# ContactSensor.net
KiCad netlist of a schematic drawn in EAGLE
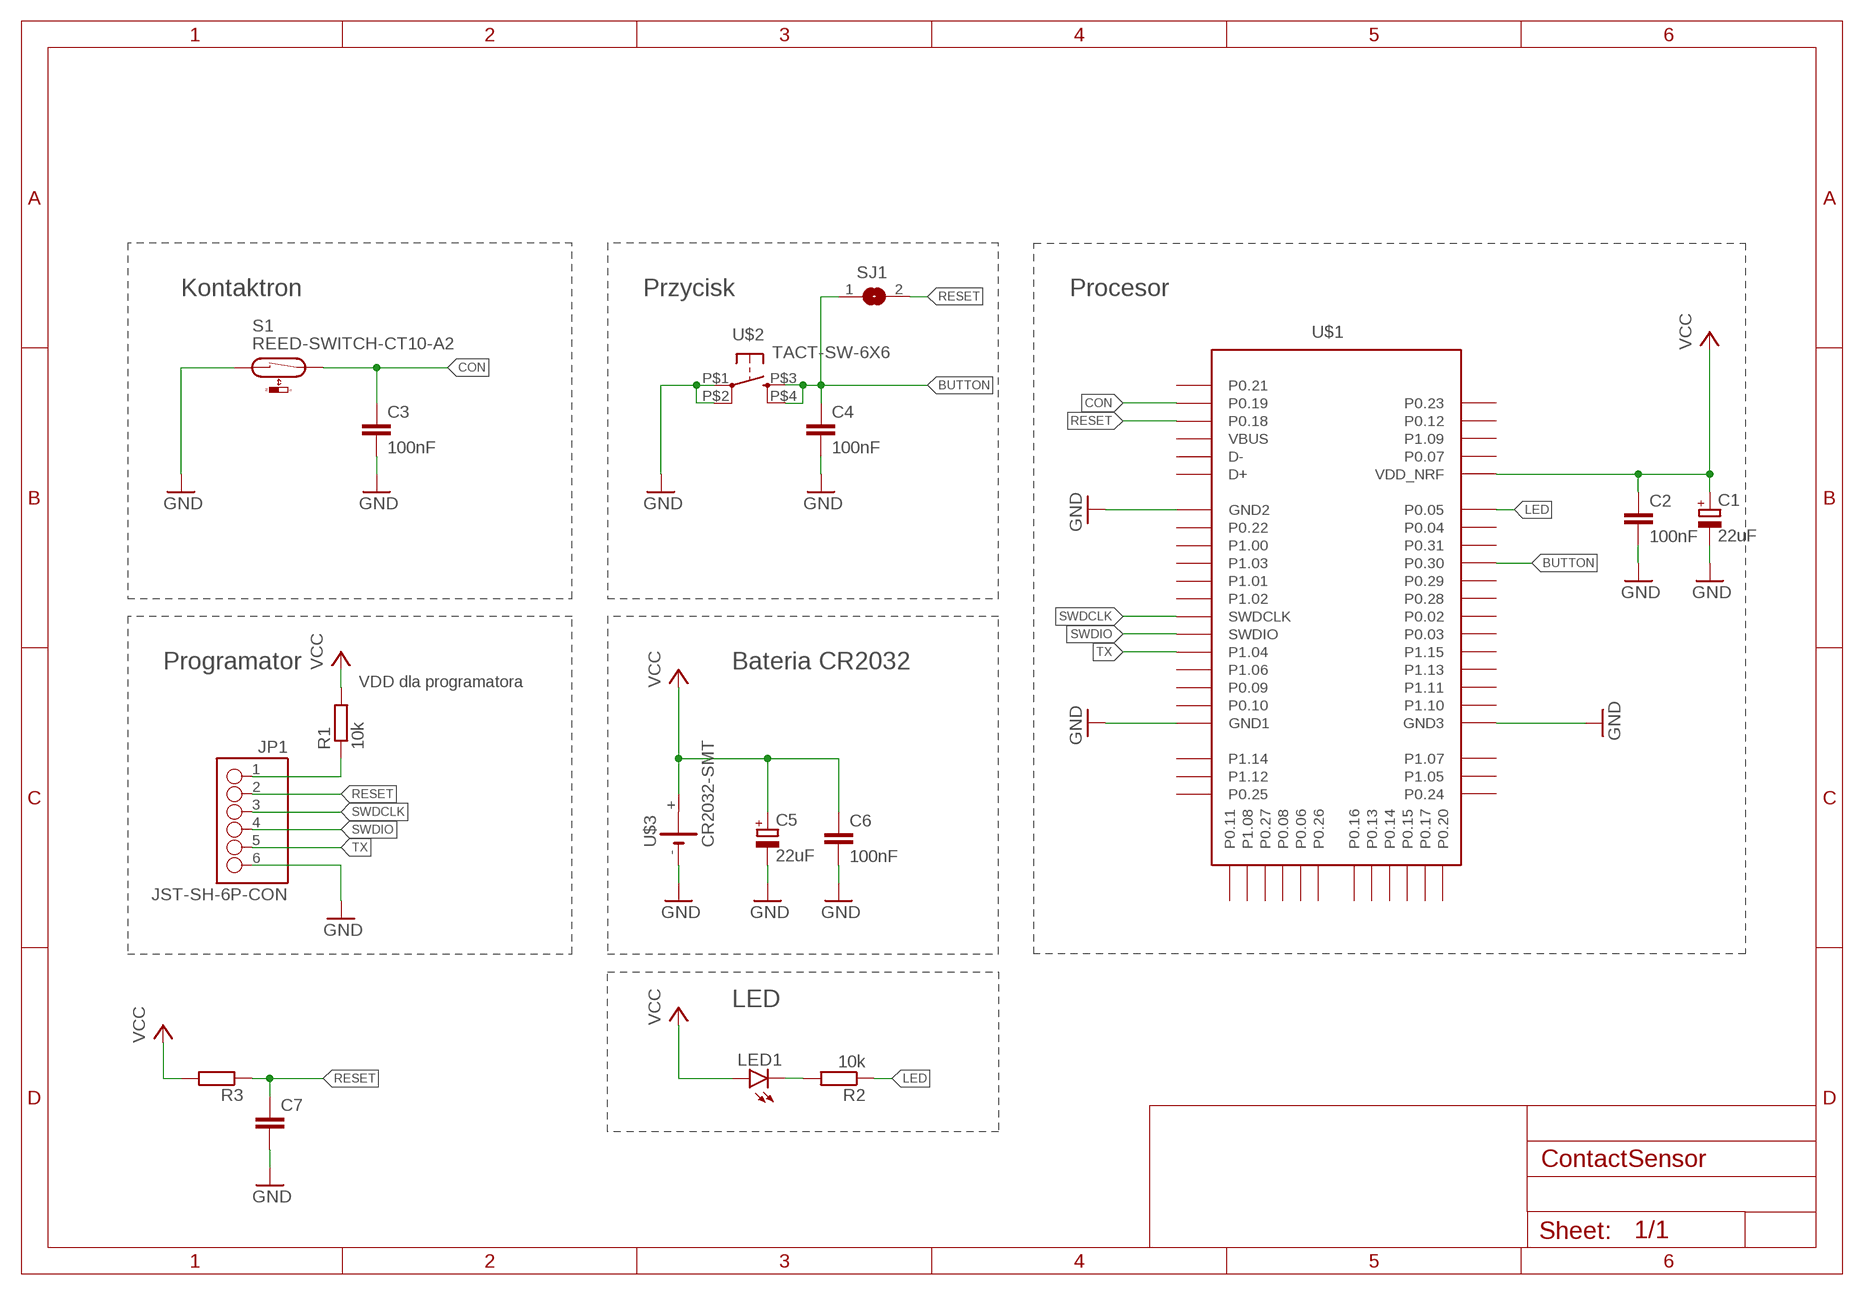
[diagram p0: schematic, sheet 1]

(export (version "E")
  (design (tool "Eeschema 10.0.6"))
  (components
    (comp (ref "C1")
      (value "22uF")
      (footprint "eagle-import:CT3528")
      (libsource (lib "eagle-import") (part "CPOL-EUCT3528"))
    )
    (comp (ref "C2")
      (value "100nF")
      (footprint "eagle-import:C0805K")
      (libsource (lib "eagle-import") (part "C-EUC0805K"))
    )
    (comp (ref "C3")
      (value "100nF")
      (footprint "eagle-import:C0805K")
      (libsource (lib "eagle-import") (part "C-EUC0805K"))
    )
    (comp (ref "C4")
      (value "100nF")
      (footprint "eagle-import:C0805K")
      (libsource (lib "eagle-import") (part "C-EUC0805K"))
    )
    (comp (ref "C5")
      (value "22uF")
      (footprint "eagle-import:CT3528")
      (libsource (lib "eagle-import") (part "CPOL-EUCT3528"))
    )
    (comp (ref "C6")
      (value "100nF")
      (footprint "eagle-import:C0805K")
      (libsource (lib "eagle-import") (part "C-EUC0805K"))
    )
    (comp (ref "C7")
      (value "C-EUC0603K")
      (footprint "eagle-import:C0603K")
      (libsource (lib "eagle-import") (part "C-EUC0603K"))
    )
    (comp (ref "JP1")
      (value "JST-SH-6P-CON")
      (footprint "eagle-import:JST-SH-6P-FOOT")
      (libsource (lib "eagle-import") (part "JST-SH-6P-CON"))
    )
    (comp (ref "LED1")
      (value "LEDCHIPLED_0603")
      (footprint "eagle-import:CHIPLED_0603")
      (libsource (lib "eagle-import") (part "LEDCHIPLED_0603"))
    )
    (comp (ref "R1")
      (value "10k")
      (footprint "eagle-import:R0603")
      (libsource (lib "eagle-import") (part "R-EU_R0603"))
    )
    (comp (ref "R2")
      (value "10k")
      (footprint "eagle-import:R0603")
      (libsource (lib "eagle-import") (part "R-EU_R0603"))
    )
    (comp (ref "R3")
      (value "R-EU_R0402")
      (footprint "eagle-import:R0402")
      (libsource (lib "eagle-import") (part "R-EU_R0402"))
    )
    (comp (ref "S1")
      (value "REED-SWITCH-CT10-A2")
      (footprint "eagle-import:CT10-A2")
      (libsource (lib "eagle-import") (part "REED-SWITCH-CT10-A2"))
    )
    (comp (ref "SJ1") (value "SJ") (footprint "eagle-import:SJ") (libsource (lib "eagle-import") (part "SJ")))
    (comp (ref "U$1")
      (value "HOLYIOT_18010")
      (footprint "eagle-import:PCBCOMPONENT_1")
      (libsource (lib "eagle-import") (part "HOLYIOT_18010"))
    )
    (comp (ref "U$2")
      (value "TACT-SW-6X6")
      (footprint "eagle-import:6X6-TACT-SWITCH-SMD")
      (libsource (lib "eagle-import") (part "TACT-SW-6X6"))
    )
    (comp (ref "U$3")
      (value "CR2032-SMT")
      (footprint "eagle-import:CR2032-SMT")
      (libsource (lib "eagle-import") (part "CR2032-SMT"))
    )
  )
  (nets
    (net (code "1") (name "BUTTON") (class "Default")
      (node (ref "C4") (pin "1") (pinfunction "1_1") (pintype "passive"))
      (node (ref "SJ1") (pin "1") (pinfunction "1_1") (pintype "passive"))
      (node (ref "U$1") (pin "P0.30") (pinfunction "P0.30_P0.30") (pintype "bidirectional"))
      (node (ref "U$2") (pin "P$3") (pinfunction "S_P$3") (pintype "passive"))
      (node (ref "U$2") (pin "P$4") (pinfunction "S1_P$4") (pintype "passive"))
    )
    (net (code "2") (name "CON") (class "Default")
      (node (ref "C3") (pin "1") (pinfunction "1_1") (pintype "passive"))
      (node (ref "S1") (pin "2") (pinfunction "2_2") (pintype "passive"))
      (node (ref "U$1") (pin "P0.19") (pinfunction "P0.19_P0.19") (pintype "bidirectional"))
    )
    (net (code "3") (name "GND") (class "Default")
      (node (ref "C1") (pin "-") (pinfunction "-_-") (pintype "passive"))
      (node (ref "C2") (pin "2") (pinfunction "2_2") (pintype "passive"))
      (node (ref "C3") (pin "2") (pinfunction "2_2") (pintype "passive"))
      (node (ref "C4") (pin "2") (pinfunction "2_2") (pintype "passive"))
      (node (ref "C5") (pin "-") (pinfunction "-_-") (pintype "passive"))
      (node (ref "C6") (pin "2") (pinfunction "2_2") (pintype "passive"))
      (node (ref "C7") (pin "2") (pinfunction "2_2") (pintype "passive"))
      (node (ref "JP1") (pin "6") (pinfunction "P$6_6") (pintype "bidirectional"))
      (node (ref "S1") (pin "1") (pinfunction "1_1") (pintype "passive"))
      (node (ref "U$1") (pin "GND") (pinfunction "GND1_GND") (pintype "bidirectional"))
      (node (ref "U$1") (pin "GND1") (pinfunction "GND2_GND1") (pintype "bidirectional"))
      (node (ref "U$1") (pin "GND2") (pinfunction "GND3_GND2") (pintype "bidirectional"))
      (node (ref "U$2") (pin "P$1") (pinfunction "P_P$1") (pintype "passive"))
      (node (ref "U$2") (pin "P$2") (pinfunction "P1_P$2") (pintype "passive"))
      (node (ref "U$3") (pin "-") (pinfunction "-_-") (pintype "passive"))
    )
    (net (code "4") (name "LED") (class "Default")
      (node (ref "R2") (pin "1") (pinfunction "1_1") (pintype "passive"))
      (node (ref "U$1") (pin "P0.05") (pinfunction "P0.05_P0.05") (pintype "bidirectional"))
    )
    (net (code "5") (name "Net-(JP1-P$1)") (class "Default")
      (node (ref "JP1") (pin "1") (pinfunction "P$1_1") (pintype "bidirectional"))
      (node (ref "R1") (pin "1") (pinfunction "1_1") (pintype "passive"))
    )
    (net (code "6") (name "Net-(LED1-PadC)") (class "Default")
      (node (ref "LED1") (pin "C") (pinfunction "C_C") (pintype "passive"))
      (node (ref "R2") (pin "2") (pinfunction "2_2") (pintype "passive"))
    )
    (net (code "7") (name "RESET") (class "Default")
      (node (ref "C7") (pin "1") (pinfunction "1_1") (pintype "passive"))
      (node (ref "JP1") (pin "2") (pinfunction "P$2_2") (pintype "bidirectional"))
      (node (ref "R3") (pin "1") (pinfunction "1_1") (pintype "passive"))
      (node (ref "SJ1") (pin "2") (pinfunction "2_2") (pintype "passive"))
      (node (ref "U$1") (pin "P0.18") (pinfunction "P0.18_P0.18") (pintype "bidirectional"))
    )
    (net (code "8") (name "SWDCLK") (class "Default")
      (node (ref "JP1") (pin "3") (pinfunction "P$3_3") (pintype "bidirectional"))
      (node (ref "U$1") (pin "SWDCLK") (pinfunction "SWDCLK_SWDCLK") (pintype "bidirectional"))
    )
    (net (code "9") (name "SWDIO") (class "Default")
      (node (ref "JP1") (pin "4") (pinfunction "P$4_4") (pintype "bidirectional"))
      (node (ref "U$1") (pin "SWDIO") (pinfunction "SWDIO_SWDIO") (pintype "bidirectional"))
    )
    (net (code "10") (name "TX") (class "Default")
      (node (ref "JP1") (pin "5") (pinfunction "P$5_5") (pintype "bidirectional"))
      (node (ref "U$1") (pin "P1.04") (pinfunction "P1.04_P1.04") (pintype "bidirectional"))
    )
    (net (code "11") (name "VCC") (class "Default")
      (node (ref "C1") (pin "+") (pinfunction "+_+") (pintype "passive"))
      (node (ref "C2") (pin "1") (pinfunction "1_1") (pintype "passive"))
      (node (ref "C5") (pin "+") (pinfunction "+_+") (pintype "passive"))
      (node (ref "C6") (pin "1") (pinfunction "1_1") (pintype "passive"))
      (node (ref "LED1") (pin "A") (pinfunction "A_A") (pintype "passive"))
      (node (ref "R1") (pin "2") (pinfunction "2_2") (pintype "passive"))
      (node (ref "R3") (pin "2") (pinfunction "2_2") (pintype "passive"))
      (node (ref "U$1") (pin "VDD_NRF") (pinfunction "VDD_NRF_VDD_NRF") (pintype "bidirectional"))
      (node (ref "U$3") (pin "+") (pinfunction "+_+") (pintype "passive"))
    )
    (net (code "12") (name "unconnected-(U$1-PadD+)") (class "Default")
      (node (ref "U$1") (pin "D+") (pinfunction "D+_D+") (pintype "bidirectional"))
    )
    (net (code "13") (name "unconnected-(U$1-PadD-)") (class "Default")
      (node (ref "U$1") (pin "D-") (pinfunction "D-_D-") (pintype "bidirectional"))
    )
    (net (code "14") (name "unconnected-(U$1-PadP0.02)") (class "Default")
      (node (ref "U$1") (pin "P0.02") (pinfunction "P0.02_P0.02") (pintype "bidirectional"))
    )
    (net (code "15") (name "unconnected-(U$1-PadP0.03)") (class "Default")
      (node (ref "U$1") (pin "P0.03") (pinfunction "P0.03_P0.03") (pintype "bidirectional"))
    )
    (net (code "16") (name "unconnected-(U$1-PadP0.04)") (class "Default")
      (node (ref "U$1") (pin "P0.04") (pinfunction "P0.04_P0.04") (pintype "bidirectional"))
    )
    (net (code "17") (name "unconnected-(U$1-PadP0.06)") (class "Default")
      (node (ref "U$1") (pin "P0.06") (pinfunction "P0.06_P0.06") (pintype "bidirectional"))
    )
    (net (code "18") (name "unconnected-(U$1-PadP0.07)") (class "Default")
      (node (ref "U$1") (pin "P0.07") (pinfunction "P0.07_P0.07") (pintype "bidirectional"))
    )
    (net (code "19") (name "unconnected-(U$1-PadP0.08)") (class "Default")
      (node (ref "U$1") (pin "P0.08") (pinfunction "P0.08_P0.08") (pintype "bidirectional"))
    )
    (net (code "20") (name "unconnected-(U$1-PadP0.09)") (class "Default")
      (node (ref "U$1") (pin "P0.09") (pinfunction "P0.09_P0.09") (pintype "bidirectional"))
    )
    (net (code "21") (name "unconnected-(U$1-PadP0.10)") (class "Default")
      (node (ref "U$1") (pin "P0.10") (pinfunction "P0.10_P0.10") (pintype "bidirectional"))
    )
    (net (code "22") (name "unconnected-(U$1-PadP0.11)") (class "Default")
      (node (ref "U$1") (pin "P0.11") (pinfunction "P0.11_P0.11") (pintype "bidirectional"))
    )
    (net (code "23") (name "unconnected-(U$1-PadP0.12)") (class "Default")
      (node (ref "U$1") (pin "P0.12") (pinfunction "P0.12_P0.12") (pintype "bidirectional"))
    )
    (net (code "24") (name "unconnected-(U$1-PadP0.13)") (class "Default")
      (node (ref "U$1") (pin "P0.13") (pinfunction "P0.13_P0.13") (pintype "bidirectional"))
    )
    (net (code "25") (name "unconnected-(U$1-PadP0.14)") (class "Default")
      (node (ref "U$1") (pin "P0.14") (pinfunction "P0.14_P0.14") (pintype "bidirectional"))
    )
    (net (code "26") (name "unconnected-(U$1-PadP0.15)") (class "Default")
      (node (ref "U$1") (pin "P0.15") (pinfunction "P0.15_P0.15") (pintype "bidirectional"))
    )
    (net (code "27") (name "unconnected-(U$1-PadP0.16)") (class "Default")
      (node (ref "U$1") (pin "P0.16") (pinfunction "P0.16_P0.16") (pintype "bidirectional"))
    )
    (net (code "28") (name "unconnected-(U$1-PadP0.17)") (class "Default")
      (node (ref "U$1") (pin "P0.17") (pinfunction "P0.17_P0.17") (pintype "bidirectional"))
    )
    (net (code "29") (name "unconnected-(U$1-PadP0.20)") (class "Default")
      (node (ref "U$1") (pin "P0.20") (pinfunction "P0.20_P0.20") (pintype "bidirectional"))
    )
    (net (code "30") (name "unconnected-(U$1-PadP0.21)") (class "Default")
      (node (ref "U$1") (pin "P0.21") (pinfunction "P0.21_P0.21") (pintype "bidirectional"))
    )
    (net (code "31") (name "unconnected-(U$1-PadP0.22)") (class "Default")
      (node (ref "U$1") (pin "P0.22") (pinfunction "P0.22_P0.22") (pintype "bidirectional"))
    )
    (net (code "32") (name "unconnected-(U$1-PadP0.23)") (class "Default")
      (node (ref "U$1") (pin "P0.23") (pinfunction "P0.23_P0.23") (pintype "bidirectional"))
    )
    (net (code "33") (name "unconnected-(U$1-PadP0.24)") (class "Default")
      (node (ref "U$1") (pin "P0.24") (pinfunction "P0.24_P0.24") (pintype "bidirectional"))
    )
    (net (code "34") (name "unconnected-(U$1-PadP0.25)") (class "Default")
      (node (ref "U$1") (pin "P0.25") (pinfunction "P0.25_P0.25") (pintype "bidirectional"))
    )
    (net (code "35") (name "unconnected-(U$1-PadP0.26)") (class "Default")
      (node (ref "U$1") (pin "P0.26") (pinfunction "P0.26_P0.26") (pintype "bidirectional"))
    )
    (net (code "36") (name "unconnected-(U$1-PadP0.27)") (class "Default")
      (node (ref "U$1") (pin "P0.27") (pinfunction "P0.27_P0.27") (pintype "bidirectional"))
    )
    (net (code "37") (name "unconnected-(U$1-PadP0.28)") (class "Default")
      (node (ref "U$1") (pin "P0.28") (pinfunction "P0.28_P0.28") (pintype "bidirectional"))
    )
    (net (code "38") (name "unconnected-(U$1-PadP0.29)") (class "Default")
      (node (ref "U$1") (pin "P0.29") (pinfunction "P0.29_P0.29") (pintype "bidirectional"))
    )
    (net (code "39") (name "unconnected-(U$1-PadP0.31)") (class "Default")
      (node (ref "U$1") (pin "P0.31") (pinfunction "P0.31_P0.31") (pintype "bidirectional"))
    )
    (net (code "40") (name "unconnected-(U$1-PadP1.00)") (class "Default")
      (node (ref "U$1") (pin "P1.00") (pinfunction "P1.00_P1.00") (pintype "bidirectional"))
    )
    (net (code "41") (name "unconnected-(U$1-PadP1.01)") (class "Default")
      (node (ref "U$1") (pin "P1.01") (pinfunction "P1.01_P1.01") (pintype "bidirectional"))
    )
    (net (code "42") (name "unconnected-(U$1-PadP1.02)") (class "Default")
      (node (ref "U$1") (pin "P1.02") (pinfunction "P1.02_P1.02") (pintype "bidirectional"))
    )
    (net (code "43") (name "unconnected-(U$1-PadP1.03)") (class "Default")
      (node (ref "U$1") (pin "P1.03") (pinfunction "P1.03_P1.03") (pintype "bidirectional"))
    )
    (net (code "44") (name "unconnected-(U$1-PadP1.05)") (class "Default")
      (node (ref "U$1") (pin "P1.05") (pinfunction "P1.05_P1.05") (pintype "bidirectional"))
    )
    (net (code "45") (name "unconnected-(U$1-PadP1.06)") (class "Default")
      (node (ref "U$1") (pin "P1.06") (pinfunction "P1.06_P1.06") (pintype "bidirectional"))
    )
    (net (code "46") (name "unconnected-(U$1-PadP1.07)") (class "Default")
      (node (ref "U$1") (pin "P1.07") (pinfunction "P1.07_P1.07") (pintype "bidirectional"))
    )
    (net (code "47") (name "unconnected-(U$1-PadP1.08)") (class "Default")
      (node (ref "U$1") (pin "P1.08") (pinfunction "P1.08_P1.08") (pintype "bidirectional"))
    )
    (net (code "48") (name "unconnected-(U$1-PadP1.09)") (class "Default")
      (node (ref "U$1") (pin "P1.09") (pinfunction "P1.09_P1.09") (pintype "bidirectional"))
    )
    (net (code "49") (name "unconnected-(U$1-PadP1.10)") (class "Default")
      (node (ref "U$1") (pin "P1.10") (pinfunction "P1.10_P1.10") (pintype "bidirectional"))
    )
    (net (code "50") (name "unconnected-(U$1-PadP1.11)") (class "Default")
      (node (ref "U$1") (pin "P1.11") (pinfunction "P1.11_P1.11") (pintype "bidirectional"))
    )
    (net (code "51") (name "unconnected-(U$1-PadP1.12)") (class "Default")
      (node (ref "U$1") (pin "P1.12") (pinfunction "P1.12_P1.12") (pintype "bidirectional"))
    )
    (net (code "52") (name "unconnected-(U$1-PadP1.13)") (class "Default")
      (node (ref "U$1") (pin "P1.13") (pinfunction "P1.13_P1.13") (pintype "bidirectional"))
    )
    (net (code "53") (name "unconnected-(U$1-PadP1.14)") (class "Default")
      (node (ref "U$1") (pin "P1.14") (pinfunction "P1.14_P1.14") (pintype "bidirectional"))
    )
    (net (code "54") (name "unconnected-(U$1-PadP1.15)") (class "Default")
      (node (ref "U$1") (pin "P1.15") (pinfunction "P1.15_P1.15") (pintype "bidirectional"))
    )
    (net (code "55") (name "unconnected-(U$1-PadVBUS)") (class "Default")
      (node (ref "U$1") (pin "VBUS") (pinfunction "VBUS_VBUS") (pintype "bidirectional"))
    )
  )
)
